# Capteurs_et_Antenne.net
KiCad netlist of a schematic drawn in Altium Designer
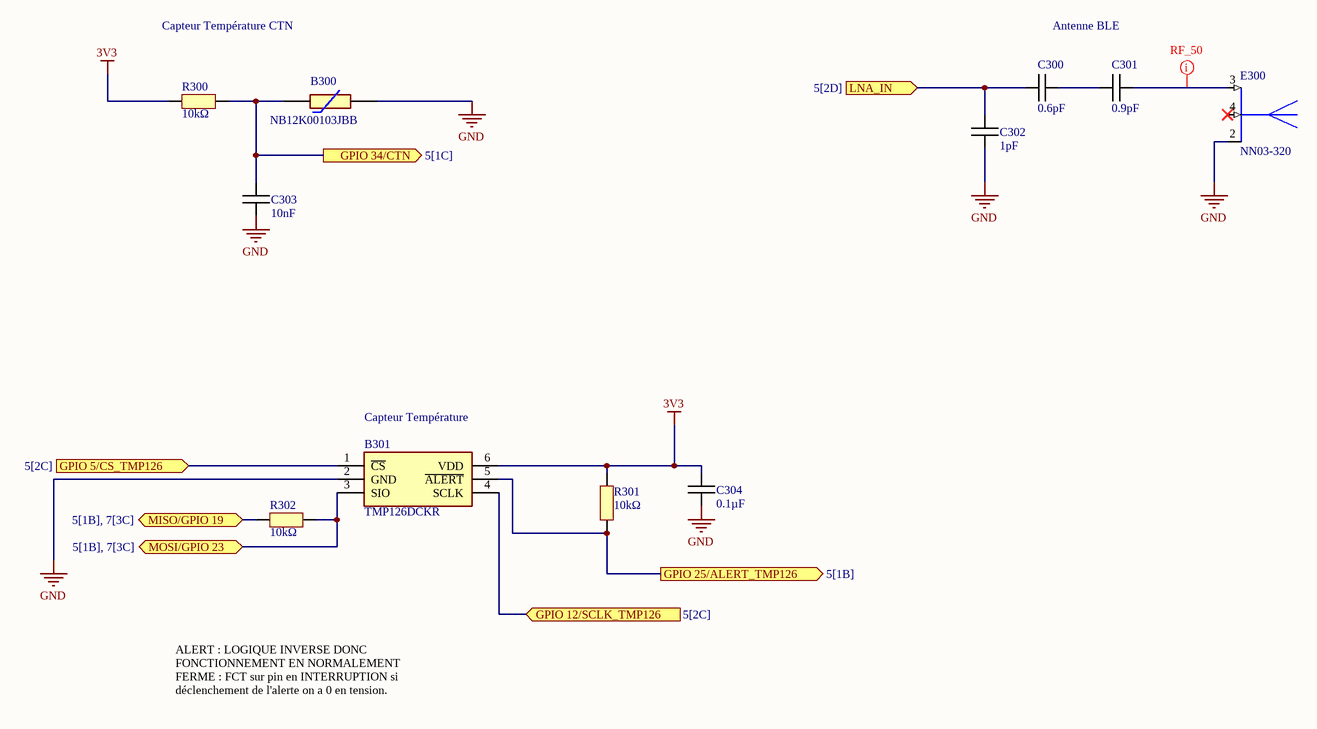
[diagram p0: Capteurs_et_Antenne.SchDoc]

(export (version "E")
  (design (tool "Eeschema 10.0.6"))
  (components
    (comp (ref "B300")
      (value "NB12K00103JBB")
      (footprint "RESC2212X50N")
      (fields (field (name "MOUSER PART NUMBER") "581-NB12K00103JBB"))
      (libsource (lib "SCHLibrary") (part "NB12K00103JBB"))
    )
    (comp (ref "B301")
      (value "TMP126DCKR")
      (footprint "SOT65P210X110-6N")
      (fields (field (name "MOUSER PART NUMBER") "595-TMP126DCKR"))
      (libsource (lib "SCHLibrary") (part "TMP126DCKR"))
    )
    (comp (ref "C300")
      (value "0.6pF")
      (footprint "CAPC1005X06N")
      (libsource (lib "SCHLibrary") (part "Capacitor"))
    )
    (comp (ref "C301")
      (value "0.9pF")
      (footprint "CAPC1005X06N")
      (libsource (lib "SCHLibrary") (part "Capacitor"))
    )
    (comp (ref "C302")
      (value "1pF")
      (footprint "CAPC1005X06N")
      (libsource (lib "SCHLibrary") (part "Capacitor"))
    )
    (comp (ref "C303")
      (value "10nF")
      (footprint "CAPC1005X06N")
      (libsource (lib "SCHLibrary") (part "Capacitor"))
    )
    (comp (ref "C304")
      (value "0.1µF")
      (footprint "CAPC1005X06N")
      (libsource (lib "SCHLibrary") (part "Capacitor"))
    )
    (comp (ref "E300")
      (value "NN03-320")
      (footprint "XCVR_NN03-320")
      (fields (field (name "MOUSER PART NUMBER") "128-NN03-320"))
      (libsource (lib "SCHLibrary") (part "NN03-320"))
    )
    (comp (ref "R300") (value "10kΩ") (footprint "RESC1005X06N") (libsource (lib "") (part "Resistor_1")))
    (comp (ref "R301")
      (value "10kΩ")
      (footprint "RESC1005X06N")
      (libsource (lib "SCHLibrary") (part "Resistor"))
    )
    (comp (ref "R302") (value "10kΩ") (footprint "RESC1005X06N") (libsource (lib "") (part "Resistor_1")))
  )
  (nets
    (net (code "1") (name "/GPIO 5{slash}CS_TMP126") (class "Default")
      (node (ref "B301") (pin "1") (pinfunction "~{CS}_1") (pintype "passive"))
    )
    (net (code "2") (name "/GPIO 12{slash}SCLK_TMP126") (class "Default")
      (node (ref "B301") (pin "4") (pinfunction "SCLK_4") (pintype "passive"))
    )
    (net (code "3") (name "/GPIO 25{slash}ALERT_TMP126") (class "Default")
      (node (ref "B301") (pin "5") (pinfunction "~{ALERT}_5") (pintype "passive"))
      (node (ref "R301") (pin "1") (pinfunction "1_1") (pintype "passive"))
    )
    (net (code "4") (name "/GPIO 34{slash}CTN") (class "Default")
      (node (ref "B300") (pin "1") (pinfunction "1_1") (pintype "passive"))
      (node (ref "C303") (pin "1") (pinfunction "1_1") (pintype "passive"))
      (node (ref "R300") (pin "2") (pinfunction "2_2") (pintype "passive"))
    )
    (net (code "5") (name "/LNA_IN") (class "Default")
      (node (ref "C300") (pin "2") (pinfunction "2_2") (pintype "passive"))
      (node (ref "C302") (pin "2") (pinfunction "2_2") (pintype "passive"))
    )
    (net (code "6") (name "/MISO{slash}GPIO 19") (class "Default")
      (node (ref "R302") (pin "1") (pinfunction "1_1") (pintype "passive"))
    )
    (net (code "7") (name "/MOSI{slash}GPIO 23") (class "Default")
      (node (ref "B301") (pin "3") (pinfunction "SIO_3") (pintype "passive"))
      (node (ref "R302") (pin "2") (pinfunction "2_2") (pintype "passive"))
    )
    (net (code "8") (name "3V3") (class "Default")
      (node (ref "B301") (pin "6") (pinfunction "VDD_6") (pintype "passive"))
      (node (ref "C304") (pin "1") (pinfunction "1_1") (pintype "passive"))
      (node (ref "R300") (pin "1") (pinfunction "1_1") (pintype "passive"))
      (node (ref "R301") (pin "2") (pinfunction "2_2") (pintype "passive"))
    )
    (net (code "9") (name "GND") (class "Default")
      (node (ref "B300") (pin "2") (pinfunction "2_2") (pintype "passive"))
      (node (ref "B301") (pin "2") (pinfunction "GND_2") (pintype "passive"))
      (node (ref "C302") (pin "1") (pinfunction "1_1") (pintype "passive"))
      (node (ref "C303") (pin "2") (pinfunction "2_2") (pintype "passive"))
      (node (ref "C304") (pin "2") (pinfunction "2_2") (pintype "passive"))
      (node (ref "E300") (pin "2") (pinfunction "GROUND_2") (pintype "power_in"))
    )
    (net (code "10") (name "Net-(C300-Pad1)") (class "Default")
      (node (ref "C300") (pin "1") (pinfunction "1_1") (pintype "passive"))
      (node (ref "C301") (pin "1") (pinfunction "1_1") (pintype "passive"))
    )
    (net (code "11") (name "Net-(E300-FEED_BLUETOOTH)") (class "Default")
      (node (ref "C301") (pin "2") (pinfunction "2_2") (pintype "passive"))
      (node (ref "E300") (pin "3") (pinfunction "FEED_BLUETOOTH_3") (pintype "input"))
    )
    (net (code "12") (name "unconnected-(E300-FEED_GNSS-Pad4)") (class "Default")
      (node (ref "E300") (pin "4") (pinfunction "FEED_GNSS_4") (pintype "input+no_connect"))
    )
  )
)
